# ScheBTL.net
KiCad netlist of a schematic drawn in Altium Designer
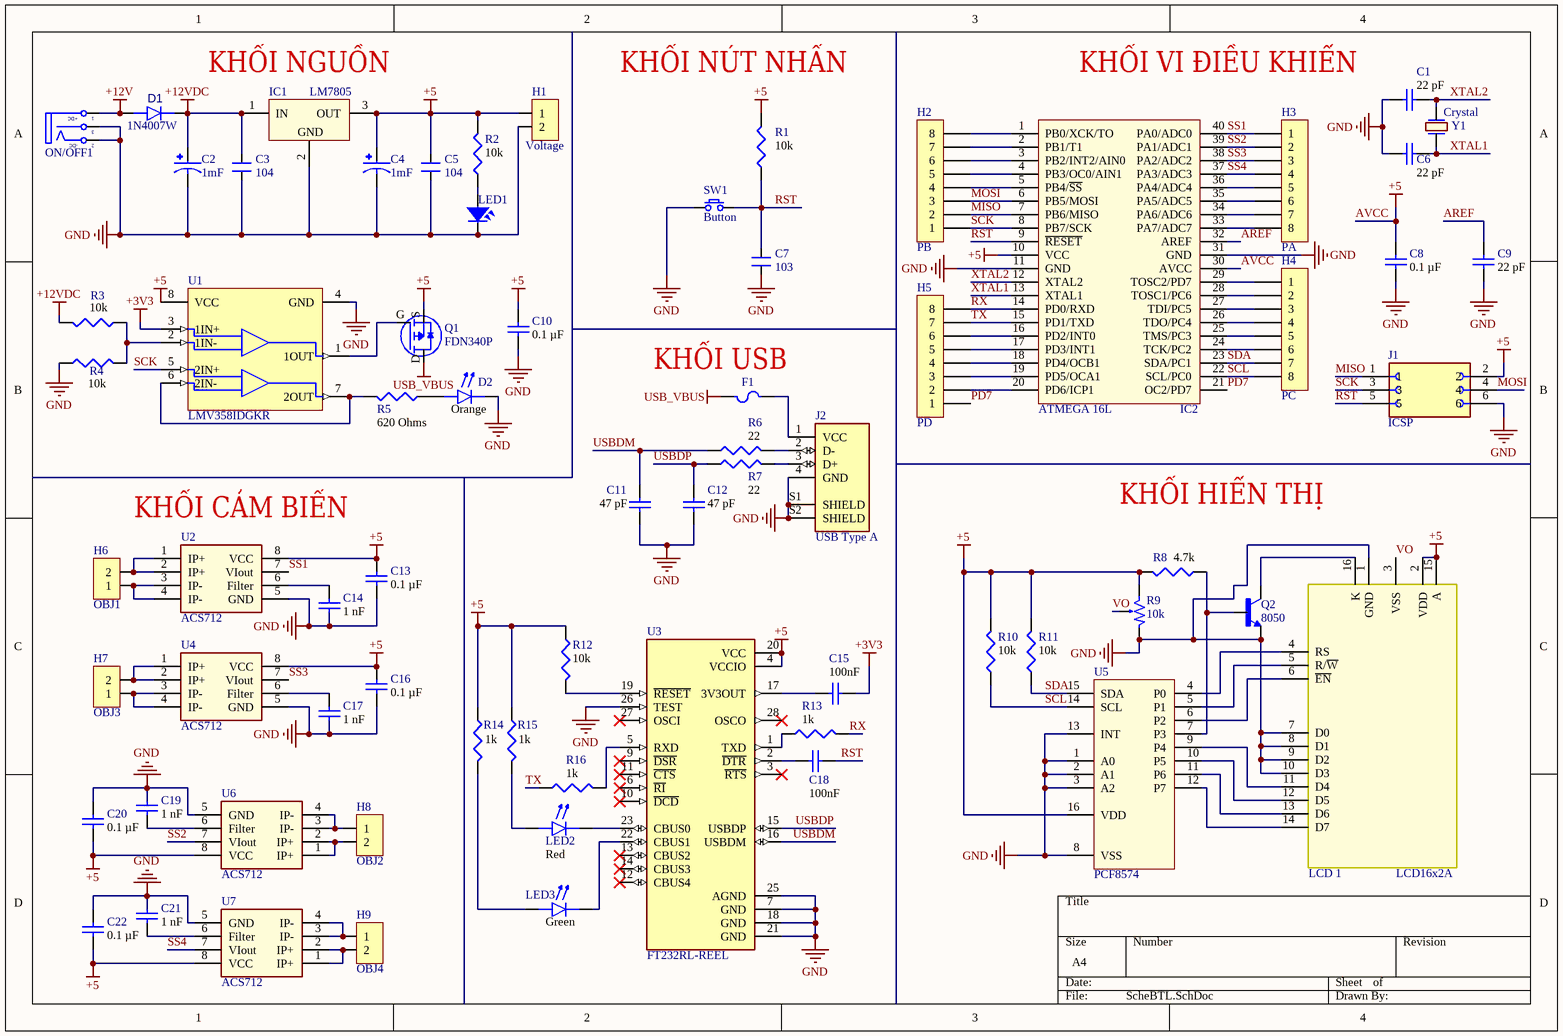
[diagram p0: ScheBTL.SchDoc]

(export (version "E")
  (design (tool "Eeschema 10.0.6"))
  (components
    (comp (ref "C1")
      (value "Capacitor")
      (footprint "0805 (2012 Metric)")
      (description "Oreki")
      (fields (field (name "CAPACITANCE") "22 pF") (field (name "TOLERANCE") "±20%"))
      (libsource (lib "[CO2037] Power Consumption Calculator Arduino Board") (part "CMP-001-00085-18"))
    )
    (comp (ref "C2")
      (value "1mF")
      (footprint "CAP_16SVPF1000M")
      (fields (field (name "MP") "16SVPF1000M"))
      (libsource (lib "16SVPF1000M") (part "16SVPF1000M"))
    )
    (comp (ref "C3")
      (value "104")
      (footprint "CN2")
      (description "Cap np 104 => 105pF")
      (libsource (lib "syhaunguyen") (part "CN2"))
    )
    (comp (ref "C4")
      (value "1mF")
      (footprint "CAP_16SVPF1000M")
      (fields (field (name "MP") "16SVPF1000M"))
      (libsource (lib "16SVPF1000M") (part "16SVPF1000M"))
    )
    (comp (ref "C5")
      (value "104")
      (footprint "CN2")
      (description "Cap np 104 => 105pF")
      (libsource (lib "syhaunguyen") (part "CN2"))
    )
    (comp (ref "C6")
      (value "Capacitor")
      (footprint "0805 (2012 Metric)")
      (description "Oreki")
      (fields (field (name "CAPACITANCE") "22 pF") (field (name "TOLERANCE") "±20%"))
      (libsource (lib "[CO2037] Power Consumption Calculator Arduino Board") (part "CMP-001-00085-18"))
    )
    (comp (ref "C7")
      (value "103")
      (footprint "CN1.5")
      (description "Cap np 682pF => 104pF")
      (libsource (lib "syhaunguyen") (part "CN1.5"))
    )
    (comp (ref "C8")
      (value "Capacitor")
      (footprint "0805 (2012 Metric)")
      (description "Oreki")
      (fields (field (name "CAPACITANCE") "0.1 µF") (field (name "TOLERANCE") "±20%"))
      (libsource (lib "[CO2037] Power Consumption Calculator Arduino Board") (part "CMP-001-00085-18"))
    )
    (comp (ref "C9")
      (value "Capacitor")
      (footprint "0805 (2012 Metric)")
      (description "Oreki")
      (fields (field (name "CAPACITANCE") "22 pF") (field (name "TOLERANCE") "±20%"))
      (libsource (lib "[CO2037] Power Consumption Calculator Arduino Board") (part "CMP-001-00085-18"))
    )
    (comp (ref "C10")
      (value "Capacitor")
      (footprint "0805 (2012 Metric)")
      (description "Oreki")
      (fields (field (name "CAPACITANCE") "0.1 µF") (field (name "TOLERANCE") "±20%"))
      (libsource (lib "[CO2037] Power Consumption Calculator Arduino Board") (part "CMP-001-00085-18"))
    )
    (comp (ref "C11")
      (value "Capacitor")
      (footprint "0805 (2012 Metric)")
      (description "Oreki")
      (fields (field (name "CAPACITANCE") "47 pF") (field (name "TOLERANCE") "±20%"))
      (libsource (lib "[CO2037] Power Consumption Calculator Arduino Board") (part "CMP-001-00085-18"))
    )
    (comp (ref "C12")
      (value "Capacitor")
      (footprint "0805 (2012 Metric)")
      (description "Oreki")
      (fields (field (name "CAPACITANCE") "47 pF") (field (name "TOLERANCE") "±20%"))
      (libsource (lib "[CO2037] Power Consumption Calculator Arduino Board") (part "CMP-001-00085-18"))
    )
    (comp (ref "C13")
      (value "Capacitor")
      (footprint "0805 (2012 Metric)")
      (description "Oreki")
      (fields (field (name "CAPACITANCE") "0.1 µF") (field (name "TOLERANCE") "±20%"))
      (libsource (lib "[CO2037] Power Consumption Calculator Arduino Board") (part "CMP-001-00085-18"))
    )
    (comp (ref "C14")
      (value "Capacitor")
      (footprint "0805 (2012 Metric)")
      (description "Oreki")
      (fields (field (name "CAPACITANCE") "1 nF") (field (name "TOLERANCE") "±20%"))
      (libsource (lib "[CO2037] Power Consumption Calculator Arduino Board") (part "CMP-001-00085-18"))
    )
    (comp (ref "C15")
      (value "Capacitor")
      (footprint "0805 (2012 Metric)")
      (description "Oreki")
      (fields (field (name "CAPACITANCE") "100nF") (field (name "TOLERANCE") "±20%"))
      (libsource (lib "[CO2037] Power Consumption Calculator Arduino Board") (part "CMP-001-00085-18"))
    )
    (comp (ref "C16")
      (value "Capacitor")
      (footprint "0805 (2012 Metric)")
      (description "Oreki")
      (fields (field (name "CAPACITANCE") "0.1 µF") (field (name "TOLERANCE") "±20%"))
      (libsource (lib "[CO2037] Power Consumption Calculator Arduino Board") (part "CMP-001-00085-18"))
    )
    (comp (ref "C17")
      (value "Capacitor")
      (footprint "0805 (2012 Metric)")
      (description "Oreki")
      (fields (field (name "CAPACITANCE") "1 nF") (field (name "TOLERANCE") "±20%"))
      (libsource (lib "[CO2037] Power Consumption Calculator Arduino Board") (part "CMP-001-00085-18"))
    )
    (comp (ref "C18")
      (value "Capacitor")
      (footprint "0805 (2012 Metric)")
      (description "Oreki")
      (fields (field (name "CAPACITANCE") "100nF") (field (name "TOLERANCE") "±20%"))
      (libsource (lib "[CO2037] Power Consumption Calculator Arduino Board") (part "CMP-001-00085-18"))
    )
    (comp (ref "C19")
      (value "Capacitor")
      (footprint "0805 (2012 Metric)")
      (description "Oreki")
      (fields (field (name "CAPACITANCE") "1 nF") (field (name "TOLERANCE") "±20%"))
      (libsource (lib "[CO2037] Power Consumption Calculator Arduino Board") (part "CMP-001-00085-18"))
    )
    (comp (ref "C20")
      (value "Capacitor")
      (footprint "0805 (2012 Metric)")
      (description "Oreki")
      (fields (field (name "CAPACITANCE") "0.1 µF") (field (name "TOLERANCE") "±20%"))
      (libsource (lib "[CO2037] Power Consumption Calculator Arduino Board") (part "CMP-001-00085-18"))
    )
    (comp (ref "C21")
      (value "Capacitor")
      (footprint "0805 (2012 Metric)")
      (description "Oreki")
      (fields (field (name "CAPACITANCE") "1 nF") (field (name "TOLERANCE") "±20%"))
      (libsource (lib "[CO2037] Power Consumption Calculator Arduino Board") (part "CMP-001-00085-18"))
    )
    (comp (ref "C22")
      (value "Capacitor")
      (footprint "0805 (2012 Metric)")
      (description "Oreki")
      (fields (field (name "CAPACITANCE") "0.1 µF") (field (name "TOLERANCE") "±20%"))
      (libsource (lib "[CO2037] Power Consumption Calculator Arduino Board") (part "CMP-001-00085-18"))
    )
    (comp (ref "D1")
      (value "Diode")
      (footprint "DO-204AL, DO-41, Axial")
      (description "Oreki")
      (fields (field (name "PART NUMBER") "1N4007W") (field (name "JLCPCB PART #") "C108803"))
      (libsource (lib "[CO2037] Power Consumption Calculator Arduino Board") (part "CMP-004-00033-6"))
    )
    (comp (ref "D2")
      (value "LED Indication - Discrete")
      (footprint "0805 (2012 Metric) Orange")
      (description "Oreki")
      (fields
        (field (name "COLOR") "Orange")
        (field (name "PART NUMBER") "17-21SURC/S530-A3/4T")
        (field (name "JLCPCB PART #") "C2943978")
      )
      (libsource (lib "[CO2037] Power Consumption Calculator Arduino Board") (part "CMP-007-00046-2"))
    )
    (comp (ref "F1")
      (value "Fuse")
      (footprint "1812 (4532 Metric), Concave")
      (description "Oreki")
      (fields (field (name "PART NUMBER") "MF-MSMF050-2") (field (name "JLCPCB PART #") "C17313"))
      (libsource (lib "[CO2037] Power Consumption Calculator Arduino Board") (part "CMP-005-00015-2"))
    )
    (comp (ref "H1")
      (value "Voltage")
      (footprint "Wire to Board, Pitch 5.00mm")
      (description "Oreki")
      (libsource (lib "[CO2037] Power Consumption Calculator Arduino Board") (part "CMP-002-00093-4"))
    )
    (comp (ref "H2")
      (value "PB")
      (footprint "Female, Through Hole, Pitch 2.54mm")
      (description "Oreki")
      (libsource (lib "[CO2037] Power Consumption Calculator Arduino Board") (part "CMP-002-00073-4"))
    )
    (comp (ref "H3")
      (value "PA")
      (footprint "Female, Through Hole, Pitch 2.54mm")
      (description "Oreki")
      (libsource (lib "") (part "CMP-002-00073-4_1"))
    )
    (comp (ref "H4")
      (value "PC")
      (footprint "Female, Through Hole, Pitch 2.54mm")
      (description "Oreki")
      (libsource (lib "") (part "CMP-002-00073-4_1"))
    )
    (comp (ref "H5")
      (value "PD")
      (footprint "Female, Through Hole, Pitch 2.54mm")
      (description "Oreki")
      (libsource (lib "[CO2037] Power Consumption Calculator Arduino Board") (part "CMP-002-00073-4"))
    )
    (comp (ref "H6")
      (value "OBJ1")
      (footprint "Wire to Board, Pitch 5.00mm")
      (description "Oreki")
      (libsource (lib "") (part "CMP-002-00093-4_1"))
    )
    (comp (ref "H7")
      (value "OBJ3")
      (footprint "Wire to Board, Pitch 5.00mm")
      (description "Oreki")
      (libsource (lib "") (part "CMP-002-00093-4_1"))
    )
    (comp (ref "H8")
      (value "OBJ2")
      (footprint "Wire to Board, Pitch 5.00mm")
      (description "Oreki")
      (libsource (lib "[CO2037] Power Consumption Calculator Arduino Board") (part "CMP-002-00093-4"))
    )
    (comp (ref "H9")
      (value "OBJ4")
      (footprint "Wire to Board, Pitch 5.00mm")
      (description "Oreki")
      (libsource (lib "[CO2037] Power Consumption Calculator Arduino Board") (part "CMP-002-00093-4"))
    )
    (comp (ref "IC1")
      (value "LM7805")
      (footprint "QTO-220")
      (description "On ap +, from + 5 to + 24VDC")
      (libsource (lib "My library altium") (part "LM78xx"))
    )
    (comp (ref "IC2")
      (value "ATMEGA 16L")
      (footprint "DIP40/W0.6")
      (description "8-Bit AVR Microcontroller with 16K Bytes of In-System Programmable Flash Memory")
      (libsource (lib "syhaunguyen") (part "Atmega16L"))
    )
    (comp (ref "J1")
      (value "ICSP")
      (footprint "SULLINS_PPTC032LFBN-RC")
      (description "6 Position Header Connector 0.100 (2.54mm) Through Hole Tin")
      (fields (field (name "MF") "Sullins Connector Solutions") (field (name "MP") "PPTC032LFBN-RC"))
      (libsource (lib "PPTC032LFBN-RC") (part "PPTC032LFBN-RC"))
    )
    (comp (ref "J2")
      (value "USB Type A")
      (footprint "GCT_USB1130-15-A_REVA")
      (fields (field (name "MP") "USB1130-15-A") (field (name "MF") "Global Connector Technology"))
      (libsource (lib "USB1130-15-A_REVA") (part "USB1130-15-A_REVA"))
    )
    (comp (ref "LCD 1")
      (value "LCD16x2A")
      (footprint "LCD16X2")
      (description "LCD dipslay 16 char, 2 line")
      (libsource (lib "syhaunguyen") (part "LCD16x2"))
    )
    (comp (ref "LED1")
      (value "LED")
      (footprint "LED-3")
      (description "LED Single colour Green and Red")
      (libsource (lib "syhaunguyen") (part "LED"))
    )
    (comp (ref "LED2")
      (value "LED Indication - Discrete")
      (footprint "0805 (2012 Metric) Red")
      (description "Oreki")
      (fields
        (field (name "COLOR") "Red")
        (field (name "PART NUMBER") "17-21SURC/S530-A3/4T")
        (field (name "JLCPCB PART #") "C2943978")
      )
      (libsource (lib "[CO2037] Power Consumption Calculator Arduino Board") (part "CMP-007-00046-2"))
    )
    (comp (ref "LED3")
      (value "LED Indication - Discrete")
      (footprint "0805 (2012 Metric) Green")
      (description "Oreki")
      (fields
        (field (name "COLOR") "Green")
        (field (name "PART NUMBER") "17-21SURC/S530-A3/4T")
        (field (name "JLCPCB PART #") "C2943978")
      )
      (libsource (lib "[CO2037] Power Consumption Calculator Arduino Board") (part "CMP-007-00046-2"))
    )
    (comp (ref "ON/OFF1")
      (value "POWER")
      (footprint "DC-IN")
      (libsource (lib "My library altium") (part "DCIN"))
    )
    (comp (ref "Q1")
      (value "Mosfet")
      (footprint "TO-236-3, SC-59, SOT-23-3")
      (description "Oreki")
      (fields (field (name "PART NUMBER") "FDN340P"))
      (libsource (lib "[CO2037] Power Consumption Calculator Arduino Board") (part "CMP-013-00039-7"))
    )
    (comp (ref "Q2")
      (value "8050")
      (footprint "TRANS_SS8050-G")
      (description "Bipolar (BJT) Transistor NPN 25 V 1.5 A 100MHz 300 mW Surface Mount SOT-23-3")
      (fields (field (name "DIGI-KEY_PART_NUMBER") "641-1790-2-ND") (field (name "MP") "SS8050G"))
      (libsource (lib "SS8050-G") (part "SS8050-G"))
    )
    (comp (ref "R1")
      (value "Resistor")
      (footprint "0805 (2012 Metric)")
      (description "Oreki")
      (fields
        (field (name "TOLERANCE") "±5%")
        (field (name "POWER") "0.125W, 1/8W")
        (field (name "RESISTANCE") "10k")
      )
      (libsource (lib "[CO2037] Power Consumption Calculator Arduino Board") (part "CMP-009-00179-11"))
    )
    (comp (ref "R2")
      (value "Resistor")
      (footprint "0805 (2012 Metric)")
      (description "Oreki")
      (fields
        (field (name "TOLERANCE") "±5%")
        (field (name "POWER") "0.125W, 1/8W")
        (field (name "RESISTANCE") "10k")
      )
      (libsource (lib "[CO2037] Power Consumption Calculator Arduino Board") (part "CMP-009-00179-11"))
    )
    (comp (ref "R3")
      (value "Resistor")
      (footprint "0805 (2012 Metric)")
      (description "Oreki")
      (fields
        (field (name "TOLERANCE") "±5%")
        (field (name "POWER") "0.125W, 1/8W")
        (field (name "RESISTANCE") "10k")
      )
      (libsource (lib "[CO2037] Power Consumption Calculator Arduino Board") (part "CMP-009-00179-11"))
    )
    (comp (ref "R4")
      (value "Resistor")
      (footprint "0805 (2012 Metric)")
      (description "Oreki")
      (fields
        (field (name "TOLERANCE") "±5%")
        (field (name "POWER") "0.125W, 1/8W")
        (field (name "RESISTANCE") "10k")
      )
      (libsource (lib "[CO2037] Power Consumption Calculator Arduino Board") (part "CMP-009-00179-11"))
    )
    (comp (ref "R5")
      (value "Resistor")
      (footprint "0805 (2012 Metric)")
      (description "Oreki")
      (fields
        (field (name "TOLERANCE") "±5%")
        (field (name "POWER") "0.125W, 1/8W")
        (field (name "RESISTANCE") "620 Ohms")
      )
      (libsource (lib "[CO2037] Power Consumption Calculator Arduino Board") (part "CMP-009-00179-11"))
    )
    (comp (ref "R6")
      (value "Resistor")
      (footprint "0805 (2012 Metric)")
      (description "Oreki")
      (fields
        (field (name "TOLERANCE") "±5%")
        (field (name "POWER") "0.125W, 1/8W")
        (field (name "RESISTANCE") "22")
      )
      (libsource (lib "[CO2037] Power Consumption Calculator Arduino Board") (part "CMP-009-00179-11"))
    )
    (comp (ref "R7")
      (value "Resistor")
      (footprint "0805 (2012 Metric)")
      (description "Oreki")
      (fields
        (field (name "TOLERANCE") "±5%")
        (field (name "POWER") "0.125W, 1/8W")
        (field (name "RESISTANCE") "22")
      )
      (libsource (lib "[CO2037] Power Consumption Calculator Arduino Board") (part "CMP-009-00179-11"))
    )
    (comp (ref "R8")
      (value "Resistor")
      (footprint "0805 (2012 Metric)")
      (description "Oreki")
      (fields
        (field (name "TOLERANCE") "±5%")
        (field (name "POWER") "0.125W, 1/8W")
        (field (name "RESISTANCE") "4.7k")
      )
      (libsource (lib "[CO2037] Power Consumption Calculator Arduino Board") (part "CMP-009-00179-11"))
    )
    (comp (ref "R9")
      (value "10k")
      (footprint "VR")
      (description "Var Resistor")
      (libsource (lib "syhaunguyen") (part "VR1"))
    )
    (comp (ref "R10")
      (value "Resistor")
      (footprint "0805 (2012 Metric)")
      (description "Oreki")
      (fields
        (field (name "TOLERANCE") "±5%")
        (field (name "POWER") "0.125W, 1/8W")
        (field (name "RESISTANCE") "10k")
      )
      (libsource (lib "[CO2037] Power Consumption Calculator Arduino Board") (part "CMP-009-00179-11"))
    )
    (comp (ref "R11")
      (value "Resistor")
      (footprint "0805 (2012 Metric)")
      (description "Oreki")
      (fields
        (field (name "TOLERANCE") "±5%")
        (field (name "POWER") "0.125W, 1/8W")
        (field (name "RESISTANCE") "10k")
      )
      (libsource (lib "[CO2037] Power Consumption Calculator Arduino Board") (part "CMP-009-00179-11"))
    )
    (comp (ref "R12")
      (value "Resistor")
      (footprint "0805 (2012 Metric)")
      (description "Oreki")
      (fields
        (field (name "TOLERANCE") "±5%")
        (field (name "POWER") "0.125W, 1/8W")
        (field (name "RESISTANCE") "10k")
      )
      (libsource (lib "[CO2037] Power Consumption Calculator Arduino Board") (part "CMP-009-00179-11"))
    )
    (comp (ref "R13")
      (value "Resistor")
      (footprint "0805 (2012 Metric)")
      (description "Oreki")
      (fields
        (field (name "TOLERANCE") "±5%")
        (field (name "POWER") "0.125W, 1/8W")
        (field (name "RESISTANCE") "1k")
      )
      (libsource (lib "[CO2037] Power Consumption Calculator Arduino Board") (part "CMP-009-00179-11"))
    )
    (comp (ref "R14")
      (value "Resistor")
      (footprint "0805 (2012 Metric)")
      (description "Oreki")
      (fields
        (field (name "TOLERANCE") "±5%")
        (field (name "POWER") "0.125W, 1/8W")
        (field (name "RESISTANCE") "1k")
      )
      (libsource (lib "[CO2037] Power Consumption Calculator Arduino Board") (part "CMP-009-00179-11"))
    )
    (comp (ref "R15")
      (value "Resistor")
      (footprint "0805 (2012 Metric)")
      (description "Oreki")
      (fields
        (field (name "TOLERANCE") "±5%")
        (field (name "POWER") "0.125W, 1/8W")
        (field (name "RESISTANCE") "1k")
      )
      (libsource (lib "[CO2037] Power Consumption Calculator Arduino Board") (part "CMP-009-00179-11"))
    )
    (comp (ref "R16")
      (value "Resistor")
      (footprint "0805 (2012 Metric)")
      (description "Oreki")
      (fields
        (field (name "TOLERANCE") "±5%")
        (field (name "POWER") "0.125W, 1/8W")
        (field (name "RESISTANCE") "1k")
      )
      (libsource (lib "[CO2037] Power Consumption Calculator Arduino Board") (part "CMP-009-00179-11"))
    )
    (comp (ref "SW1")
      (value "Button")
      (footprint "SW/2/DIP")
      (description "Tact switch 2 pin")
      (libsource (lib "chipfc_altium_libs") (part "SW SPST"))
    )
    (comp (ref "U1")
      (value "LMV358")
      (footprint "8-TSSOP, 8-MSOP")
      (description "Oreki")
      (fields (field (name "PART NUMBER") "LMV358IDGKR") (field (name "JLCPCB PART #") "C5145253"))
      (libsource (lib "[CO2037] Power Consumption Calculator Arduino Board") (part "CMP-031-00028-4"))
    )
    (comp (ref "U2") (value "ACS712") (footprint "SOIC-8") (libsource (lib "") (part "ACS712_1")))
    (comp (ref "U3")
      (value "FT232RL-REEL")
      (footprint "SOP65P780X200-28N")
      (description "USB Bridge, USB to UART USB 2.0 UART Interface 28-SSOP")
      (fields (field (name "MF") "FTDI,"))
      (libsource (lib "FT232RL-REEL") (part "FT232RL-REEL"))
    )
    (comp (ref "U4") (value "ACS712") (footprint "SOIC-8") (libsource (lib "") (part "ACS712_1")))
    (comp (ref "U5")
      (value "PCF8574")
      (footprint "SO16/PCF8574AT")
      (description "Remote 8-bit I/O expander for I2C-bus with interrupt")
      (fields (field (name "PART NO") "PCF8574AT/3"))
      (libsource (lib "ic_io_interface") (part "PCF8574AT"))
    )
    (comp (ref "U6")
      (value "ACS712")
      (footprint "SOIC-8")
      (libsource (lib "chipfc_altium_libs") (part "ACS712"))
    )
    (comp (ref "U7")
      (value "ACS712")
      (footprint "SOIC-8")
      (libsource (lib "chipfc_altium_libs") (part "ACS712"))
    )
    (comp (ref "Y1")
      (value "Crystal")
      (footprint "Crystal HC49S DIP")
      (libsource (lib "chipfc_altium_libs") (part "Crystal"))
    )
  )
  (nets
    (net (code "1") (name "+3V3") (class "Default")
      (node (ref "C15") (pin "1") (pinfunction "1_1") (pintype "passive"))
      (node (ref "U1") (pin "3") (pinfunction "1IN+_3") (pintype "input"))
    )
    (net (code "2") (name "+5") (class "Default")
      (node (ref "C10") (pin "2") (pinfunction "2_2") (pintype "passive"))
      (node (ref "C13") (pin "2") (pinfunction "2_2") (pintype "passive"))
      (node (ref "C16") (pin "2") (pinfunction "2_2") (pintype "passive"))
      (node (ref "C20") (pin "1") (pinfunction "1_1") (pintype "passive"))
      (node (ref "C22") (pin "1") (pinfunction "1_1") (pintype "passive"))
      (node (ref "C4") (pin "1") (pinfunction "1_1") (pintype "passive"))
      (node (ref "C5") (pin "2") (pinfunction "2_2") (pintype "passive"))
      (node (ref "C8") (pin "2") (pinfunction "2_2") (pintype "passive"))
      (node (ref "H1") (pin "1") (pinfunction "1_1") (pintype "passive"))
      (node (ref "IC1") (pin "3") (pinfunction "OUT_3") (pintype "passive"))
      (node (ref "IC2") (pin "10") (pinfunction "VCC_10") (pintype "passive"))
      (node (ref "IC2") (pin "30") (pinfunction "AVCC_30") (pintype "passive"))
      (node (ref "J1") (pin "2") (pinfunction "2_2") (pintype "passive"))
      (node (ref "LCD 1") (pin "15") (pinfunction "A_15") (pintype "passive"))
      (node (ref "LCD 1") (pin "2") (pinfunction "VDD_2") (pintype "passive"))
      (node (ref "Q1") (pin "S") (pinfunction "S_S") (pintype "passive"))
      (node (ref "R1") (pin "2") (pinfunction "2_2") (pintype "passive"))
      (node (ref "R10") (pin "2") (pinfunction "2_2") (pintype "passive"))
      (node (ref "R11") (pin "2") (pinfunction "2_2") (pintype "passive"))
      (node (ref "R12") (pin "1") (pinfunction "1_1") (pintype "passive"))
      (node (ref "R14") (pin "1") (pinfunction "1_1") (pintype "passive"))
      (node (ref "R15") (pin "1") (pinfunction "1_1") (pintype "passive"))
      (node (ref "R2") (pin "2") (pinfunction "2_2") (pintype "passive"))
      (node (ref "R8") (pin "2") (pinfunction "2_2") (pintype "passive"))
      (node (ref "R9") (pin "3") (pinfunction "3_3") (pintype "passive"))
      (node (ref "U1") (pin "8") (pinfunction "VCC_8") (pintype "passive"))
      (node (ref "U2") (pin "8") (pinfunction "VCC_8") (pintype "passive"))
      (node (ref "U3") (pin "20") (pinfunction "VCC_20") (pintype "power_in"))
      (node (ref "U3") (pin "4") (pinfunction "VCCIO_4") (pintype "power_in"))
      (node (ref "U4") (pin "8") (pinfunction "VCC_8") (pintype "passive"))
      (node (ref "U5") (pin "16") (pinfunction "VDD_16") (pintype "passive"))
      (node (ref "U6") (pin "8") (pinfunction "VCC_8") (pintype "passive"))
      (node (ref "U7") (pin "8") (pinfunction "VCC_8") (pintype "passive"))
    )
    (net (code "3") (name "+12V") (class "Default")
      (node (ref "D1") (pin "2") (pinfunction "A_2") (pintype "passive"))
      (node (ref "ON/OFF1") (pin "1") (pinfunction "T_1") (pintype "passive"))
    )
    (net (code "4") (name "+12VDC") (class "Default")
      (node (ref "C2") (pin "1") (pinfunction "1_1") (pintype "passive"))
      (node (ref "C3") (pin "2") (pinfunction "2_2") (pintype "passive"))
      (node (ref "D1") (pin "1") (pinfunction "K_1") (pintype "passive"))
      (node (ref "IC1") (pin "1") (pinfunction "IN_1") (pintype "passive"))
      (node (ref "R3") (pin "2") (pinfunction "2_2") (pintype "passive"))
    )
    (net (code "5") (name "/AREF") (class "Default")
      (node (ref "C9") (pin "2") (pinfunction "2_2") (pintype "passive"))
      (node (ref "IC2") (pin "32") (pinfunction "AREF_32") (pintype "passive"))
    )
    (net (code "6") (name "/MISO") (class "Default")
      (node (ref "H2") (pin "2") (pinfunction "2_2") (pintype "passive"))
      (node (ref "IC2") (pin "7") (pinfunction "PB6/MISO_7") (pintype "passive"))
      (node (ref "J1") (pin "1") (pinfunction "1_1") (pintype "passive"))
    )
    (net (code "7") (name "/MOSI") (class "Default")
      (node (ref "H2") (pin "3") (pinfunction "3_3") (pintype "passive"))
      (node (ref "IC2") (pin "6") (pinfunction "PB5/MOSI_6") (pintype "passive"))
      (node (ref "J1") (pin "4") (pinfunction "4_4") (pintype "passive"))
    )
    (net (code "8") (name "/PD7") (class "Default")
      (node (ref "H5") (pin "1") (pinfunction "1_1") (pintype "passive"))
      (node (ref "IC2") (pin "21") (pinfunction "OC2/PD7_21") (pintype "passive"))
    )
    (net (code "9") (name "/RST") (class "Default")
      (node (ref "C18") (pin "1") (pinfunction "1_1") (pintype "passive"))
      (node (ref "C7") (pin "2") (pinfunction "2_2") (pintype "passive"))
      (node (ref "IC2") (pin "9") (pinfunction "~{RESET}_9") (pintype "passive"))
      (node (ref "J1") (pin "5") (pinfunction "5_5") (pintype "passive"))
      (node (ref "R1") (pin "1") (pinfunction "1_1") (pintype "passive"))
      (node (ref "SW1") (pin "2") (pinfunction "2_2") (pintype "passive"))
    )
    (net (code "10") (name "/RX") (class "Default")
      (node (ref "H5") (pin "8") (pinfunction "8_8") (pintype "passive"))
      (node (ref "IC2") (pin "14") (pinfunction "PD0/RXD_14") (pintype "passive"))
      (node (ref "R13") (pin "2") (pinfunction "2_2") (pintype "passive"))
    )
    (net (code "11") (name "/SCK") (class "Default")
      (node (ref "H2") (pin "1") (pinfunction "1_1") (pintype "passive"))
      (node (ref "IC2") (pin "8") (pinfunction "PB7/SCK_8") (pintype "passive"))
      (node (ref "J1") (pin "3") (pinfunction "3_3") (pintype "passive"))
      (node (ref "U1") (pin "5") (pinfunction "2IN+_5") (pintype "input"))
    )
    (net (code "12") (name "/SCL") (class "Default")
      (node (ref "H4") (pin "8") (pinfunction "8_8") (pintype "passive"))
      (node (ref "IC2") (pin "22") (pinfunction "SCL/PC0_22") (pintype "passive"))
      (node (ref "R10") (pin "1") (pinfunction "1_1") (pintype "passive"))
      (node (ref "U5") (pin "14") (pinfunction "SCL_14") (pintype "passive"))
    )
    (net (code "13") (name "/SDA") (class "Default")
      (node (ref "H4") (pin "7") (pinfunction "7_7") (pintype "passive"))
      (node (ref "IC2") (pin "23") (pinfunction "SDA/PC1_23") (pintype "passive"))
      (node (ref "R11") (pin "1") (pinfunction "1_1") (pintype "passive"))
      (node (ref "U5") (pin "15") (pinfunction "SDA_15") (pintype "passive"))
    )
    (net (code "14") (name "/SS1") (class "Default")
      (node (ref "H3") (pin "1") (pinfunction "1_1") (pintype "passive"))
      (node (ref "IC2") (pin "40") (pinfunction "PA0/ADC0_40") (pintype "passive"))
      (node (ref "U2") (pin "7") (pinfunction "VIout_7") (pintype "passive"))
    )
    (net (code "15") (name "/SS2") (class "Default")
      (node (ref "H3") (pin "2") (pinfunction "2_2") (pintype "passive"))
      (node (ref "IC2") (pin "39") (pinfunction "PA1/ADC1_39") (pintype "passive"))
      (node (ref "U6") (pin "7") (pinfunction "VIout_7") (pintype "passive"))
    )
    (net (code "16") (name "/SS3") (class "Default")
      (node (ref "H3") (pin "3") (pinfunction "3_3") (pintype "passive"))
      (node (ref "IC2") (pin "38") (pinfunction "PA2/ADC2_38") (pintype "passive"))
      (node (ref "U4") (pin "7") (pinfunction "VIout_7") (pintype "passive"))
    )
    (net (code "17") (name "/SS4") (class "Default")
      (node (ref "H3") (pin "4") (pinfunction "4_4") (pintype "passive"))
      (node (ref "IC2") (pin "37") (pinfunction "PA3/ADC3_37") (pintype "passive"))
      (node (ref "U7") (pin "7") (pinfunction "VIout_7") (pintype "passive"))
    )
    (net (code "18") (name "/TX") (class "Default")
      (node (ref "H5") (pin "7") (pinfunction "7_7") (pintype "passive"))
      (node (ref "IC2") (pin "15") (pinfunction "PD1/TXD_15") (pintype "passive"))
      (node (ref "R16") (pin "1") (pinfunction "1_1") (pintype "passive"))
    )
    (net (code "19") (name "/USBDM") (class "Default")
      (node (ref "C11") (pin "2") (pinfunction "2_2") (pintype "passive"))
      (node (ref "R6") (pin "1") (pinfunction "1_1") (pintype "passive"))
      (node (ref "U3") (pin "16") (pinfunction "USBDM_16") (pintype "bidirectional"))
    )
    (net (code "20") (name "/USBDP") (class "Default")
      (node (ref "C12") (pin "2") (pinfunction "2_2") (pintype "passive"))
      (node (ref "R7") (pin "1") (pinfunction "1_1") (pintype "passive"))
      (node (ref "U3") (pin "15") (pinfunction "USBDP_15") (pintype "bidirectional"))
    )
    (net (code "21") (name "/VO") (class "Default")
      (node (ref "LCD 1") (pin "3") (pinfunction "VSS_3") (pintype "passive"))
      (node (ref "R9") (pin "2") (pinfunction "2_2") (pintype "passive"))
    )
    (net (code "22") (name "/XTAL1") (class "Default")
      (node (ref "C6") (pin "1") (pinfunction "1_1") (pintype "passive"))
      (node (ref "IC2") (pin "13") (pinfunction "XTAL1_13") (pintype "passive"))
      (node (ref "Y1") (pin "1") (pinfunction "1_1") (pintype "passive"))
    )
    (net (code "23") (name "/XTAL2") (class "Default")
      (node (ref "C1") (pin "1") (pinfunction "1_1") (pintype "passive"))
      (node (ref "IC2") (pin "12") (pinfunction "XTAL2_12") (pintype "passive"))
      (node (ref "Y1") (pin "2") (pinfunction "2_2") (pintype "passive"))
    )
    (net (code "24") (name "GND") (class "Default")
      (node (ref "C1") (pin "2") (pinfunction "2_2") (pintype "passive"))
      (node (ref "C10") (pin "1") (pinfunction "1_1") (pintype "passive"))
      (node (ref "C11") (pin "1") (pinfunction "1_1") (pintype "passive"))
      (node (ref "C12") (pin "1") (pinfunction "1_1") (pintype "passive"))
      (node (ref "C13") (pin "1") (pinfunction "1_1") (pintype "passive"))
      (node (ref "C14") (pin "1") (pinfunction "1_1") (pintype "passive"))
      (node (ref "C16") (pin "1") (pinfunction "1_1") (pintype "passive"))
      (node (ref "C17") (pin "1") (pinfunction "1_1") (pintype "passive"))
      (node (ref "C19") (pin "2") (pinfunction "2_2") (pintype "passive"))
      (node (ref "C2") (pin "2") (pinfunction "2_2") (pintype "passive"))
      (node (ref "C20") (pin "2") (pinfunction "2_2") (pintype "passive"))
      (node (ref "C21") (pin "2") (pinfunction "2_2") (pintype "passive"))
      (node (ref "C22") (pin "2") (pinfunction "2_2") (pintype "passive"))
      (node (ref "C3") (pin "1") (pinfunction "1_1") (pintype "passive"))
      (node (ref "C4") (pin "2") (pinfunction "2_2") (pintype "passive"))
      (node (ref "C5") (pin "1") (pinfunction "1_1") (pintype "passive"))
      (node (ref "C6") (pin "2") (pinfunction "2_2") (pintype "passive"))
      (node (ref "C7") (pin "1") (pinfunction "1_1") (pintype "passive"))
      (node (ref "C8") (pin "1") (pinfunction "1_1") (pintype "passive"))
      (node (ref "C9") (pin "1") (pinfunction "1_1") (pintype "passive"))
      (node (ref "D2") (pin "1") (pinfunction "K_1") (pintype "passive"))
      (node (ref "H1") (pin "2") (pinfunction "2_2") (pintype "passive"))
      (node (ref "IC1") (pin "2") (pinfunction "GND_2") (pintype "passive"))
      (node (ref "IC2") (pin "11") (pinfunction "GND_11") (pintype "passive"))
      (node (ref "IC2") (pin "31") (pinfunction "GND_31") (pintype "passive"))
      (node (ref "J1") (pin "6") (pinfunction "6_6") (pintype "passive"))
      (node (ref "J2") (pin "4") (pinfunction "GND_4") (pintype "power_in"))
      (node (ref "J2") (pin "S1") (pinfunction "SHIELD_S1") (pintype "passive"))
      (node (ref "J2") (pin "S2") (pinfunction "SHIELD_S2") (pintype "passive"))
      (node (ref "LCD 1") (pin "1") (pinfunction "GND_1") (pintype "passive"))
      (node (ref "LCD 1") (pin "10") (pinfunction "D3_10") (pintype "passive"))
      (node (ref "LCD 1") (pin "7") (pinfunction "D0_7") (pintype "passive"))
      (node (ref "LCD 1") (pin "8") (pinfunction "D1_8") (pintype "passive"))
      (node (ref "LCD 1") (pin "9") (pinfunction "D2_9") (pintype "passive"))
      (node (ref "LED1") (pin "2") (pinfunction "2_2") (pintype "passive"))
      (node (ref "ON/OFF1") (pin "2") (pinfunction "TN_2") (pintype "passive"))
      (node (ref "ON/OFF1") (pin "3") (pinfunction "S_3") (pintype "power_in"))
      (node (ref "Q2") (pin "2") (pinfunction "E_2") (pintype "passive"))
      (node (ref "R4") (pin "1") (pinfunction "1_1") (pintype "passive"))
      (node (ref "R9") (pin "1") (pinfunction "1_1") (pintype "passive"))
      (node (ref "SW1") (pin "1") (pinfunction "1_1") (pintype "passive"))
      (node (ref "U1") (pin "4") (pinfunction "GND_4") (pintype "passive"))
      (node (ref "U2") (pin "5") (pinfunction "GND_5") (pintype "passive"))
      (node (ref "U3") (pin "18") (pinfunction "GND_18") (pintype "power_in"))
      (node (ref "U3") (pin "21") (pinfunction "GND_21") (pintype "power_in"))
      (node (ref "U3") (pin "25") (pinfunction "AGND_25") (pintype "power_in"))
      (node (ref "U3") (pin "26") (pinfunction "TEST_26") (pintype "input"))
      (node (ref "U3") (pin "7") (pinfunction "GND_7") (pintype "power_in"))
      (node (ref "U4") (pin "5") (pinfunction "GND_5") (pintype "passive"))
      (node (ref "U5") (pin "1") (pinfunction "A0_1") (pintype "passive"))
      (node (ref "U5") (pin "13") (pinfunction "INT_13") (pintype "passive"))
      (node (ref "U5") (pin "2") (pinfunction "A1_2") (pintype "passive"))
      (node (ref "U5") (pin "3") (pinfunction "A2_3") (pintype "passive"))
      (node (ref "U5") (pin "8") (pinfunction "VSS_8") (pintype "passive"))
      (node (ref "U6") (pin "5") (pinfunction "GND_5") (pintype "passive"))
      (node (ref "U7") (pin "5") (pinfunction "GND_5") (pintype "passive"))
    )
    (net (code "25") (name "Net-(D2-A)") (class "Default")
      (node (ref "D2") (pin "2") (pinfunction "A_2") (pintype "passive"))
      (node (ref "R5") (pin "1") (pinfunction "1_1") (pintype "passive"))
    )
    (net (code "26") (name "Net-(H6-Pad1)") (class "Default")
      (node (ref "H6") (pin "1") (pinfunction "1_1") (pintype "passive"))
      (node (ref "U2") (pin "3") (pinfunction "IP-_3") (pintype "passive"))
      (node (ref "U2") (pin "4") (pinfunction "IP-_4") (pintype "passive"))
    )
    (net (code "27") (name "Net-(H6-Pad2)") (class "Default")
      (node (ref "H6") (pin "2") (pinfunction "2_2") (pintype "passive"))
      (node (ref "U2") (pin "1") (pinfunction "IP+_1") (pintype "passive"))
      (node (ref "U2") (pin "2") (pinfunction "IP+_2") (pintype "passive"))
    )
    (net (code "28") (name "Net-(H7-Pad1)") (class "Default")
      (node (ref "H7") (pin "1") (pinfunction "1_1") (pintype "passive"))
      (node (ref "U4") (pin "3") (pinfunction "IP-_3") (pintype "passive"))
      (node (ref "U4") (pin "4") (pinfunction "IP-_4") (pintype "passive"))
    )
    (net (code "29") (name "Net-(H7-Pad2)") (class "Default")
      (node (ref "H7") (pin "2") (pinfunction "2_2") (pintype "passive"))
      (node (ref "U4") (pin "1") (pinfunction "IP+_1") (pintype "passive"))
      (node (ref "U4") (pin "2") (pinfunction "IP+_2") (pintype "passive"))
    )
    (net (code "30") (name "Net-(H8-Pad1)") (class "Default")
      (node (ref "H8") (pin "1") (pinfunction "1_1") (pintype "passive"))
      (node (ref "U6") (pin "3") (pinfunction "IP-_3") (pintype "passive"))
      (node (ref "U6") (pin "4") (pinfunction "IP-_4") (pintype "passive"))
    )
    (net (code "31") (name "Net-(H8-Pad2)") (class "Default")
      (node (ref "H8") (pin "2") (pinfunction "2_2") (pintype "passive"))
      (node (ref "U6") (pin "1") (pinfunction "IP+_1") (pintype "passive"))
      (node (ref "U6") (pin "2") (pinfunction "IP+_2") (pintype "passive"))
    )
    (net (code "32") (name "Net-(H9-Pad1)") (class "Default")
      (node (ref "H9") (pin "1") (pinfunction "1_1") (pintype "passive"))
      (node (ref "U7") (pin "3") (pinfunction "IP-_3") (pintype "passive"))
      (node (ref "U7") (pin "4") (pinfunction "IP-_4") (pintype "passive"))
    )
    (net (code "33") (name "Net-(H9-Pad2)") (class "Default")
      (node (ref "H9") (pin "2") (pinfunction "2_2") (pintype "passive"))
      (node (ref "U7") (pin "1") (pinfunction "IP+_1") (pintype "passive"))
      (node (ref "U7") (pin "2") (pinfunction "IP+_2") (pintype "passive"))
    )
    (net (code "34") (name "Net-(IC2-PA4{slash}ADC4)") (class "Default")
      (node (ref "H3") (pin "5") (pinfunction "5_5") (pintype "passive"))
      (node (ref "IC2") (pin "36") (pinfunction "PA4/ADC4_36") (pintype "passive"))
    )
    (net (code "35") (name "Net-(IC2-PA5{slash}ADC5)") (class "Default")
      (node (ref "H3") (pin "6") (pinfunction "6_6") (pintype "passive"))
      (node (ref "IC2") (pin "35") (pinfunction "PA5/ADC5_35") (pintype "passive"))
    )
    (net (code "36") (name "Net-(IC2-PA6{slash}ADC6)") (class "Default")
      (node (ref "H3") (pin "7") (pinfunction "7_7") (pintype "passive"))
      (node (ref "IC2") (pin "34") (pinfunction "PA6/ADC6_34") (pintype "passive"))
    )
    (net (code "37") (name "Net-(IC2-PA7{slash}ADC7)") (class "Default")
      (node (ref "H3") (pin "8") (pinfunction "8_8") (pintype "passive"))
      (node (ref "IC2") (pin "33") (pinfunction "PA7/ADC7_33") (pintype "passive"))
    )
    (net (code "38") (name "Net-(IC2-PB0{slash}XCK{slash}TO)") (class "Default")
      (node (ref "H2") (pin "8") (pinfunction "8_8") (pintype "passive"))
      (node (ref "IC2") (pin "1") (pinfunction "PB0/XCK/TO_1") (pintype "passive"))
    )
    (net (code "39") (name "Net-(IC2-PB1{slash}T1)") (class "Default")
      (node (ref "H2") (pin "7") (pinfunction "7_7") (pintype "passive"))
      (node (ref "IC2") (pin "2") (pinfunction "PB1/T1_2") (pintype "passive"))
    )
    (net (code "40") (name "Net-(IC2-PB2{slash}INT2{slash}AIN0)") (class "Default")
      (node (ref "H2") (pin "6") (pinfunction "6_6") (pintype "passive"))
      (node (ref "IC2") (pin "3") (pinfunction "PB2/INT2/AIN0_3") (pintype "passive"))
    )
    (net (code "41") (name "Net-(IC2-PB3{slash}OC0{slash}AIN1)") (class "Default")
      (node (ref "H2") (pin "5") (pinfunction "5_5") (pintype "passive"))
      (node (ref "IC2") (pin "4") (pinfunction "PB3/OC0/AIN1_4") (pintype "passive"))
    )
    (net (code "42") (name "Net-(IC2-PB4{slash}~{SS})") (class "Default")
      (node (ref "H2") (pin "4") (pinfunction "4_4") (pintype "passive"))
      (node (ref "IC2") (pin "5") (pinfunction "PB4/~{SS}_5") (pintype "passive"))
    )
    (net (code "43") (name "Net-(IC2-PD2{slash}INT0)") (class "Default")
      (node (ref "H5") (pin "6") (pinfunction "6_6") (pintype "passive"))
      (node (ref "IC2") (pin "16") (pinfunction "PD2/INT0_16") (pintype "passive"))
    )
    (net (code "44") (name "Net-(IC2-PD3{slash}INT1)") (class "Default")
      (node (ref "H5") (pin "5") (pinfunction "5_5") (pintype "passive"))
      (node (ref "IC2") (pin "17") (pinfunction "PD3/INT1_17") (pintype "passive"))
    )
    (net (code "45") (name "Net-(IC2-PD4{slash}OCB1)") (class "Default")
      (node (ref "H5") (pin "4") (pinfunction "4_4") (pintype "passive"))
      (node (ref "IC2") (pin "18") (pinfunction "PD4/OCB1_18") (pintype "passive"))
    )
    (net (code "46") (name "Net-(IC2-PD5{slash}OCA1)") (class "Default")
      (node (ref "H5") (pin "3") (pinfunction "3_3") (pintype "passive"))
      (node (ref "IC2") (pin "19") (pinfunction "PD5/OCA1_19") (pintype "passive"))
    )
    (net (code "47") (name "Net-(IC2-PD6{slash}ICP1)") (class "Default")
      (node (ref "H5") (pin "2") (pinfunction "2_2") (pintype "passive"))
      (node (ref "IC2") (pin "20") (pinfunction "PD6/ICP1_20") (pintype "passive"))
    )
    (net (code "48") (name "Net-(IC2-TCK{slash}PC2)") (class "Default")
      (node (ref "H4") (pin "6") (pinfunction "6_6") (pintype "passive"))
      (node (ref "IC2") (pin "24") (pinfunction "TCK/PC2_24") (pintype "passive"))
    )
    (net (code "49") (name "Net-(IC2-TDI{slash}PC5)") (class "Default")
      (node (ref "H4") (pin "3") (pinfunction "3_3") (pintype "passive"))
      (node (ref "IC2") (pin "27") (pinfunction "TDI/PC5_27") (pintype "passive"))
    )
    (net (code "50") (name "Net-(IC2-TDO{slash}PC4)") (class "Default")
      (node (ref "H4") (pin "4") (pinfunction "4_4") (pintype "passive"))
      (node (ref "IC2") (pin "26") (pinfunction "TDO/PC4_26") (pintype "passive"))
    )
    (net (code "51") (name "Net-(IC2-TMS{slash}PC3)") (class "Default")
      (node (ref "H4") (pin "5") (pinfunction "5_5") (pintype "passive"))
      (node (ref "IC2") (pin "25") (pinfunction "TMS/PC3_25") (pintype "passive"))
    )
    (net (code "52") (name "Net-(IC2-TOSC1{slash}PC6)") (class "Default")
      (node (ref "H4") (pin "2") (pinfunction "2_2") (pintype "passive"))
      (node (ref "IC2") (pin "28") (pinfunction "TOSC1/PC6_28") (pintype "passive"))
    )
    (net (code "53") (name "Net-(IC2-TOSC2{slash}PD7)") (class "Default")
      (node (ref "H4") (pin "1") (pinfunction "1_1") (pintype "passive"))
      (node (ref "IC2") (pin "29") (pinfunction "TOSC2/PD7_29") (pintype "passive"))
    )
    (net (code "54") (name "Net-(J2-D+)") (class "Default")
      (node (ref "J2") (pin "3") (pinfunction "D+_3") (pintype "bidirectional"))
      (node (ref "R7") (pin "2") (pinfunction "2_2") (pintype "passive"))
    )
    (net (code "55") (name "Net-(J2-D-)") (class "Default")
      (node (ref "J2") (pin "2") (pinfunction "D-_2") (pintype "bidirectional"))
      (node (ref "R6") (pin "2") (pinfunction "2_2") (pintype "passive"))
    )
    (net (code "56") (name "Net-(J2-VCC)") (class "Default")
      (node (ref "F1") (pin "2") (pinfunction "2_2") (pintype "passive"))
      (node (ref "J2") (pin "1") (pinfunction "VCC_1") (pintype "power_in"))
    )
    (net (code "57") (name "Net-(LCD 1-D4)") (class "Default")
      (node (ref "LCD 1") (pin "11") (pinfunction "D4_11") (pintype "passive"))
      (node (ref "U5") (pin "9") (pinfunction "P4_9") (pintype "passive"))
    )
    (net (code "58") (name "Net-(LCD 1-D5)") (class "Default")
      (node (ref "LCD 1") (pin "12") (pinfunction "D5_12") (pintype "passive"))
      (node (ref "U5") (pin "10") (pinfunction "P5_10") (pintype "passive"))
    )
    (net (code "59") (name "Net-(LCD 1-D6)") (class "Default")
      (node (ref "LCD 1") (pin "13") (pinfunction "D6_13") (pintype "passive"))
      (node (ref "U5") (pin "11") (pinfunction "P6_11") (pintype "passive"))
    )
    (net (code "60") (name "Net-(LCD 1-D7)") (class "Default")
      (node (ref "LCD 1") (pin "14") (pinfunction "D7_14") (pintype "passive"))
      (node (ref "U5") (pin "12") (pinfunction "P7_12") (pintype "passive"))
    )
    (net (code "61") (name "Net-(LCD 1-K)") (class "Default")
      (node (ref "LCD 1") (pin "16") (pinfunction "K_16") (pintype "passive"))
      (node (ref "Q2") (pin "3") (pinfunction "C_3") (pintype "passive"))
    )
    (net (code "62") (name "Net-(LCD 1-RS)") (class "Default")
      (node (ref "LCD 1") (pin "4") (pinfunction "RS_4") (pintype "passive"))
      (node (ref "U5") (pin "4") (pinfunction "P0_4") (pintype "passive"))
    )
    (net (code "63") (name "Net-(LCD 1-R{slash}~{W})") (class "Default")
      (node (ref "LCD 1") (pin "5") (pinfunction "R/~{W}_5") (pintype "passive"))
      (node (ref "U5") (pin "5") (pinfunction "P1_5") (pintype "passive"))
    )
    (net (code "64") (name "Net-(LCD 1-~{EN})") (class "Default")
      (node (ref "LCD 1") (pin "6") (pinfunction "~{EN}_6") (pintype "passive"))
      (node (ref "U5") (pin "6") (pinfunction "P2_6") (pintype "passive"))
    )
    (net (code "65") (name "Net-(LED1-Pad1)") (class "Default")
      (node (ref "LED1") (pin "1") (pinfunction "1_1") (pintype "passive"))
      (node (ref "R2") (pin "1") (pinfunction "1_1") (pintype "passive"))
    )
    (net (code "66") (name "Net-(LED2-A)") (class "Default")
      (node (ref "LED2") (pin "2") (pinfunction "A_2") (pintype "passive"))
      (node (ref "R15") (pin "2") (pinfunction "2_2") (pintype "passive"))
    )
    (net (code "67") (name "Net-(LED2-K)") (class "Default")
      (node (ref "LED2") (pin "1") (pinfunction "K_1") (pintype "passive"))
      (node (ref "U3") (pin "23") (pinfunction "CBUS0_23") (pintype "bidirectional"))
    )
    (net (code "68") (name "Net-(LED3-A)") (class "Default")
      (node (ref "LED3") (pin "2") (pinfunction "A_2") (pintype "passive"))
      (node (ref "R14") (pin "2") (pinfunction "2_2") (pintype "passive"))
    )
    (net (code "69") (name "Net-(LED3-K)") (class "Default")
      (node (ref "LED3") (pin "1") (pinfunction "K_1") (pintype "passive"))
      (node (ref "U3") (pin "22") (pinfunction "CBUS1_22") (pintype "bidirectional"))
    )
    (net (code "70") (name "Net-(Q2-B)") (class "Default")
      (node (ref "Q2") (pin "1") (pinfunction "B_1") (pintype "passive"))
      (node (ref "R8") (pin "1") (pinfunction "1_1") (pintype "passive"))
      (node (ref "U5") (pin "7") (pinfunction "P3_7") (pintype "passive"))
    )
    (net (code "71") (name "Net-(U1-1IN-)") (class "Default")
      (node (ref "R3") (pin "1") (pinfunction "1_1") (pintype "passive"))
      (node (ref "R4") (pin "2") (pinfunction "2_2") (pintype "passive"))
      (node (ref "U1") (pin "2") (pinfunction "1IN-_2") (pintype "input"))
    )
    (net (code "72") (name "Net-(U1-1OUT)") (class "Default")
      (node (ref "Q1") (pin "G") (pinfunction "G_G") (pintype "passive"))
      (node (ref "U1") (pin "1") (pinfunction "1OUT_1") (pintype "output"))
    )
    (net (code "73") (name "Net-(U1-2IN-)") (class "Default")
      (node (ref "R5") (pin "2") (pinfunction "2_2") (pintype "passive"))
      (node (ref "U1") (pin "6") (pinfunction "2IN-_6") (pintype "input"))
      (node (ref "U1") (pin "7") (pinfunction "2OUT_7") (pintype "output"))
    )
    (net (code "74") (name "Net-(U2-Filter)") (class "Default")
      (node (ref "C14") (pin "2") (pinfunction "2_2") (pintype "passive"))
      (node (ref "U2") (pin "6") (pinfunction "Filter_6") (pintype "passive"))
    )
    (net (code "75") (name "Net-(U3-3V3OUT)") (class "Default")
      (node (ref "C15") (pin "2") (pinfunction "2_2") (pintype "passive"))
      (node (ref "U3") (pin "17") (pinfunction "3V3OUT_17") (pintype "output"))
    )
    (net (code "76") (name "Net-(U3-RXD)") (class "Default")
      (node (ref "R16") (pin "2") (pinfunction "2_2") (pintype "passive"))
      (node (ref "U3") (pin "5") (pinfunction "RXD_5") (pintype "input"))
    )
    (net (code "77") (name "Net-(U3-TXD)") (class "Default")
      (node (ref "R13") (pin "1") (pinfunction "1_1") (pintype "passive"))
      (node (ref "U3") (pin "1") (pinfunction "TXD_1") (pintype "output"))
    )
    (net (code "78") (name "Net-(U3-~{DTR})") (class "Default")
      (node (ref "C18") (pin "2") (pinfunction "2_2") (pintype "passive"))
      (node (ref "U3") (pin "2") (pinfunction "~{DTR}_2") (pintype "output"))
    )
    (net (code "79") (name "Net-(U3-~{RESET})") (class "Default")
      (node (ref "R12") (pin "2") (pinfunction "2_2") (pintype "passive"))
      (node (ref "U3") (pin "19") (pinfunction "~{RESET}_19") (pintype "input"))
    )
    (net (code "80") (name "Net-(U4-Filter)") (class "Default")
      (node (ref "C17") (pin "2") (pinfunction "2_2") (pintype "passive"))
      (node (ref "U4") (pin "6") (pinfunction "Filter_6") (pintype "passive"))
    )
    (net (code "81") (name "Net-(U6-Filter)") (class "Default")
      (node (ref "C19") (pin "1") (pinfunction "1_1") (pintype "passive"))
      (node (ref "U6") (pin "6") (pinfunction "Filter_6") (pintype "passive"))
    )
    (net (code "82") (name "Net-(U7-Filter)") (class "Default")
      (node (ref "C21") (pin "1") (pinfunction "1_1") (pintype "passive"))
      (node (ref "U7") (pin "6") (pinfunction "Filter_6") (pintype "passive"))
    )
    (net (code "83") (name "USB_VBUS") (class "Default")
      (node (ref "F1") (pin "1") (pinfunction "1_1") (pintype "passive"))
      (node (ref "Q1") (pin "D") (pinfunction "D_D") (pintype "passive"))
    )
    (net (code "84") (name "unconnected-(U3-CBUS2-Pad13)") (class "Default")
      (node (ref "U3") (pin "13") (pinfunction "CBUS2_13") (pintype "bidirectional+no_connect"))
    )
    (net (code "85") (name "unconnected-(U3-CBUS3-Pad14)") (class "Default")
      (node (ref "U3") (pin "14") (pinfunction "CBUS3_14") (pintype "bidirectional+no_connect"))
    )
    (net (code "86") (name "unconnected-(U3-CBUS4-Pad12)") (class "Default")
      (node (ref "U3") (pin "12") (pinfunction "CBUS4_12") (pintype "bidirectional+no_connect"))
    )
    (net (code "87") (name "unconnected-(U3-OSCI-Pad27)") (class "Default")
      (node (ref "U3") (pin "27") (pinfunction "OSCI_27") (pintype "input+no_connect"))
    )
    (net (code "88") (name "unconnected-(U3-OSCO-Pad28)") (class "Default")
      (node (ref "U3") (pin "28") (pinfunction "OSCO_28") (pintype "output+no_connect"))
    )
    (net (code "89") (name "unconnected-(U3-~{CTS}-Pad11)") (class "Default")
      (node (ref "U3") (pin "11") (pinfunction "~{CTS}_11") (pintype "input+no_connect"))
    )
    (net (code "90") (name "unconnected-(U3-~{DCD}-Pad10)") (class "Default")
      (node (ref "U3") (pin "10") (pinfunction "~{DCD}_10") (pintype "input+no_connect"))
    )
    (net (code "91") (name "unconnected-(U3-~{DSR}-Pad9)") (class "Default")
      (node (ref "U3") (pin "9") (pinfunction "~{DSR}_9") (pintype "input+no_connect"))
    )
    (net (code "92") (name "unconnected-(U3-~{RI}-Pad6)") (class "Default")
      (node (ref "U3") (pin "6") (pinfunction "~{RI}_6") (pintype "input+no_connect"))
    )
    (net (code "93") (name "unconnected-(U3-~{RTS}-Pad3)") (class "Default")
      (node (ref "U3") (pin "3") (pinfunction "~{RTS}_3") (pintype "output+no_connect"))
    )
  )
)
